# i2c-bridge-atmega-2.net
KiCad netlist of a schematic drawn in EAGLE
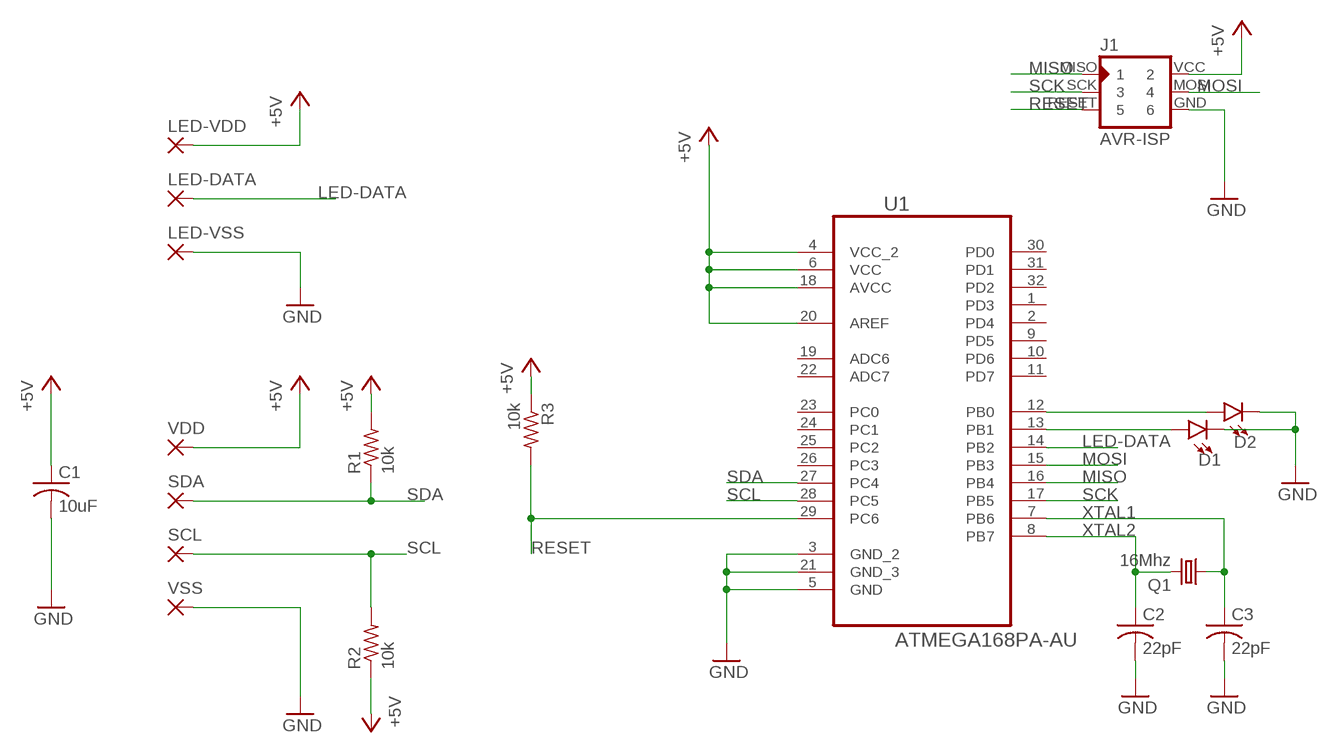
[diagram p0: schematic, sheet 1]

(export (version "E")
  (design (tool "Eeschema 10.0.6"))
  (components
    (comp (ref "C1")
      (value "10uF")
      (footprint "eagle-import:C0805")
      (libsource (lib "eagle-import") (part "C-USC0805"))
    )
    (comp (ref "C2")
      (value "22pF")
      (footprint "eagle-import:C0805")
      (libsource (lib "eagle-import") (part "C-USC0805"))
    )
    (comp (ref "C3")
      (value "22pF")
      (footprint "eagle-import:C0805")
      (libsource (lib "eagle-import") (part "C-USC0805"))
    )
    (comp (ref "D1")
      (value "WHITE")
      (footprint "eagle-import:LED-1206")
      (libsource (lib "eagle-import") (part "LED-WHITE1206"))
    )
    (comp (ref "D2")
      (value "WHITE")
      (footprint "eagle-import:LED-1206")
      (libsource (lib "eagle-import") (part "LED-WHITE1206"))
    )
    (comp (ref "J1")
      (value "AVR-ISP")
      (footprint "eagle-import:AVR-ISP-6PIN-SMAILL-SILK")
      (libsource (lib "eagle-import") (part "AVR-ISP-6PINAVR-ISP-6PIN-SMALL-SILK"))
    )
    (comp (ref "LED-DATA")
      (value "SMD2")
      (footprint "eagle-import:SMD1,27-2,54")
      (libsource (lib "eagle-import") (part "SMD2"))
    )
    (comp (ref "LED-VDD")
      (value "SMD2")
      (footprint "eagle-import:SMD1,27-2,54")
      (libsource (lib "eagle-import") (part "SMD2"))
    )
    (comp (ref "LED-VSS")
      (value "SMD2")
      (footprint "eagle-import:SMD1,27-2,54")
      (libsource (lib "eagle-import") (part "SMD2"))
    )
    (comp (ref "Q1")
      (value "16Mhz")
      (footprint "eagle-import:CSM-7X-DU")
      (libsource (lib "eagle-import") (part "CSM-7X-DU"))
    )
    (comp (ref "R1")
      (value "10k")
      (footprint "eagle-import:R0805")
      (libsource (lib "eagle-import") (part "R-US_R0805"))
    )
    (comp (ref "R2")
      (value "10k")
      (footprint "eagle-import:R0805")
      (libsource (lib "eagle-import") (part "R-US_R0805"))
    )
    (comp (ref "R3")
      (value "10k")
      (footprint "eagle-import:R0805")
      (libsource (lib "eagle-import") (part "R-US_R0805"))
    )
    (comp (ref "SCL")
      (value "SMD2")
      (footprint "eagle-import:SMD1,27-2,54")
      (libsource (lib "eagle-import") (part "SMD2"))
    )
    (comp (ref "SDA")
      (value "SMD2")
      (footprint "eagle-import:SMD1,27-2,54")
      (libsource (lib "eagle-import") (part "SMD2"))
    )
    (comp (ref "U1")
      (value "ATMEGA168PA-AU")
      (footprint "eagle-import:QFP80P900X900X120-32N")
      (libsource (lib "eagle-import") (part "ATMEGA168PA-AU"))
    )
    (comp (ref "VDD")
      (value "SMD2")
      (footprint "eagle-import:SMD1,27-2,54")
      (libsource (lib "eagle-import") (part "SMD2"))
    )
    (comp (ref "VSS")
      (value "SMD2")
      (footprint "eagle-import:SMD1,27-2,54")
      (libsource (lib "eagle-import") (part "SMD2"))
    )
  )
  (nets
    (net (code "1") (name "+5V") (class "Default")
      (node (ref "C1") (pin "1") (pinfunction "1_1") (pintype "passive"))
      (node (ref "J1") (pin "VCC") (pinfunction "2_VCC") (pintype "passive"))
      (node (ref "LED-VDD") (pin "1") (pinfunction "P_1") (pintype "passive"))
      (node (ref "R1") (pin "2") (pinfunction "2_2") (pintype "passive"))
      (node (ref "R2") (pin "1") (pinfunction "1_1") (pintype "passive"))
      (node (ref "R3") (pin "1") (pinfunction "1_1") (pintype "passive"))
      (node (ref "U1") (pin "18") (pinfunction "AVCC_18") (pintype "power_in"))
      (node (ref "U1") (pin "20") (pinfunction "AREF_20") (pintype "input"))
      (node (ref "U1") (pin "4") (pinfunction "VCC_2_4") (pintype "power_in"))
      (node (ref "U1") (pin "6") (pinfunction "VCC_6") (pintype "power_in"))
      (node (ref "VDD") (pin "1") (pinfunction "P_1") (pintype "passive"))
    )
    (net (code "2") (name "/LED-DATA") (class "Default")
      (node (ref "LED-DATA") (pin "1") (pinfunction "P_1") (pintype "passive"))
      (node (ref "U1") (pin "14") (pinfunction "PB2_14") (pintype "bidirectional"))
    )
    (net (code "3") (name "/MISO") (class "Default")
      (node (ref "J1") (pin "MISO") (pinfunction "1_MISO") (pintype "passive"))
      (node (ref "U1") (pin "16") (pinfunction "PB4_16") (pintype "bidirectional"))
    )
    (net (code "4") (name "/MOSI") (class "Default")
      (node (ref "J1") (pin "MOSI") (pinfunction "4_MOSI") (pintype "passive"))
      (node (ref "U1") (pin "15") (pinfunction "PB3_15") (pintype "bidirectional"))
    )
    (net (code "5") (name "/RESET") (class "Default")
      (node (ref "J1") (pin "RESET") (pinfunction "5_RESET") (pintype "passive"))
      (node (ref "R3") (pin "2") (pinfunction "2_2") (pintype "passive"))
      (node (ref "U1") (pin "29") (pinfunction "PC6_29") (pintype "bidirectional"))
    )
    (net (code "6") (name "/SCK") (class "Default")
      (node (ref "J1") (pin "SCK") (pinfunction "3_SCK") (pintype "passive"))
      (node (ref "U1") (pin "17") (pinfunction "PB5_17") (pintype "bidirectional"))
    )
    (net (code "7") (name "/SCL") (class "Default")
      (node (ref "R2") (pin "2") (pinfunction "2_2") (pintype "passive"))
      (node (ref "SCL") (pin "1") (pinfunction "P_1") (pintype "passive"))
      (node (ref "U1") (pin "28") (pinfunction "PC5_28") (pintype "bidirectional"))
    )
    (net (code "8") (name "/SDA") (class "Default")
      (node (ref "R1") (pin "1") (pinfunction "1_1") (pintype "passive"))
      (node (ref "SDA") (pin "1") (pinfunction "P_1") (pintype "passive"))
      (node (ref "U1") (pin "27") (pinfunction "PC4_27") (pintype "bidirectional"))
    )
    (net (code "9") (name "/XTAL1") (class "Default")
      (node (ref "C3") (pin "1") (pinfunction "1_1") (pintype "passive"))
      (node (ref "Q1") (pin "1") (pinfunction "1_1") (pintype "passive"))
      (node (ref "U1") (pin "7") (pinfunction "PB6_7") (pintype "bidirectional"))
    )
    (net (code "10") (name "/XTAL2") (class "Default")
      (node (ref "C2") (pin "1") (pinfunction "1_1") (pintype "passive"))
      (node (ref "Q1") (pin "2") (pinfunction "2_2") (pintype "passive"))
      (node (ref "U1") (pin "8") (pinfunction "PB7_8") (pintype "bidirectional"))
    )
    (net (code "11") (name "GND") (class "Default")
      (node (ref "C1") (pin "2") (pinfunction "2_2") (pintype "passive"))
      (node (ref "C2") (pin "2") (pinfunction "2_2") (pintype "passive"))
      (node (ref "C3") (pin "2") (pinfunction "2_2") (pintype "passive"))
      (node (ref "D1") (pin "C") (pinfunction "C_C") (pintype "passive"))
      (node (ref "D2") (pin "C") (pinfunction "C_C") (pintype "passive"))
      (node (ref "J1") (pin "GND") (pinfunction "6_GND") (pintype "passive"))
      (node (ref "LED-VSS") (pin "1") (pinfunction "P_1") (pintype "passive"))
      (node (ref "U1") (pin "21") (pinfunction "GND_3_21") (pintype "passive"))
      (node (ref "U1") (pin "3") (pinfunction "GND_2_3") (pintype "passive"))
      (node (ref "U1") (pin "5") (pinfunction "GND_5") (pintype "passive"))
      (node (ref "VSS") (pin "1") (pinfunction "P_1") (pintype "passive"))
    )
    (net (code "12") (name "Net-(U1-PB0)") (class "Default")
      (node (ref "D2") (pin "A") (pinfunction "A_A") (pintype "passive"))
      (node (ref "U1") (pin "12") (pinfunction "PB0_12") (pintype "bidirectional"))
    )
    (net (code "13") (name "Net-(U1-PB1)") (class "Default")
      (node (ref "D1") (pin "A") (pinfunction "A_A") (pintype "passive"))
      (node (ref "U1") (pin "13") (pinfunction "PB1_13") (pintype "bidirectional"))
    )
    (net (code "14") (name "unconnected-(U1-ADC6-Pad19)") (class "Default")
      (node (ref "U1") (pin "19") (pinfunction "ADC6_19") (pintype "input"))
    )
    (net (code "15") (name "unconnected-(U1-ADC7-Pad22)") (class "Default")
      (node (ref "U1") (pin "22") (pinfunction "ADC7_22") (pintype "input"))
    )
    (net (code "16") (name "unconnected-(U1-PC0-Pad23)") (class "Default")
      (node (ref "U1") (pin "23") (pinfunction "PC0_23") (pintype "bidirectional"))
    )
    (net (code "17") (name "unconnected-(U1-PC1-Pad24)") (class "Default")
      (node (ref "U1") (pin "24") (pinfunction "PC1_24") (pintype "bidirectional"))
    )
    (net (code "18") (name "unconnected-(U1-PC2-Pad25)") (class "Default")
      (node (ref "U1") (pin "25") (pinfunction "PC2_25") (pintype "bidirectional"))
    )
    (net (code "19") (name "unconnected-(U1-PC3-Pad26)") (class "Default")
      (node (ref "U1") (pin "26") (pinfunction "PC3_26") (pintype "bidirectional"))
    )
    (net (code "20") (name "unconnected-(U1-PD0-Pad30)") (class "Default")
      (node (ref "U1") (pin "30") (pinfunction "PD0_30") (pintype "bidirectional"))
    )
    (net (code "21") (name "unconnected-(U1-PD1-Pad31)") (class "Default")
      (node (ref "U1") (pin "31") (pinfunction "PD1_31") (pintype "bidirectional"))
    )
    (net (code "22") (name "unconnected-(U1-PD2-Pad32)") (class "Default")
      (node (ref "U1") (pin "32") (pinfunction "PD2_32") (pintype "bidirectional"))
    )
    (net (code "23") (name "unconnected-(U1-PD3-Pad1)") (class "Default")
      (node (ref "U1") (pin "1") (pinfunction "PD3_1") (pintype "bidirectional"))
    )
    (net (code "24") (name "unconnected-(U1-PD4-Pad2)") (class "Default")
      (node (ref "U1") (pin "2") (pinfunction "PD4_2") (pintype "bidirectional"))
    )
    (net (code "25") (name "unconnected-(U1-PD5-Pad9)") (class "Default")
      (node (ref "U1") (pin "9") (pinfunction "PD5_9") (pintype "bidirectional"))
    )
    (net (code "26") (name "unconnected-(U1-PD6-Pad10)") (class "Default")
      (node (ref "U1") (pin "10") (pinfunction "PD6_10") (pintype "bidirectional"))
    )
    (net (code "27") (name "unconnected-(U1-PD7-Pad11)") (class "Default")
      (node (ref "U1") (pin "11") (pinfunction "PD7_11") (pintype "bidirectional"))
    )
  )
)
